# TOP_SHEET.net
KiCad netlist of a schematic drawn in Altium Designer
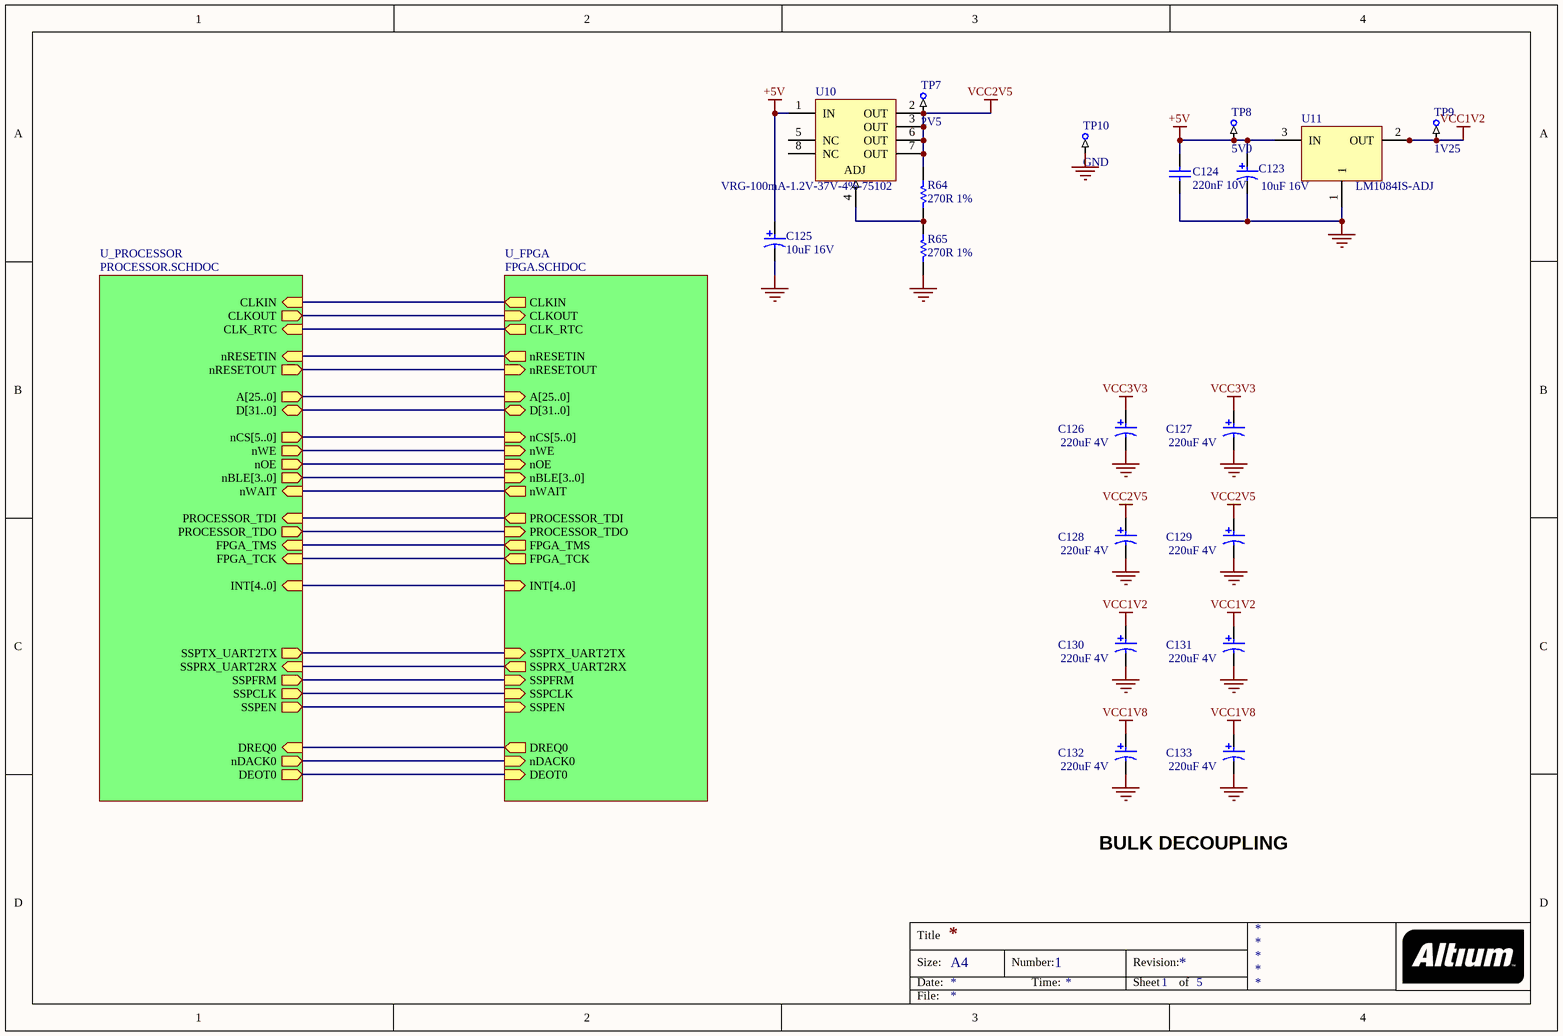
[diagram p0: TOP_SHEET.SCHDOC]

(export (version "E")
  (design (tool "Eeschema 10.0.6"))
  (components
    (comp (ref "C123")
      (value "10uF 16V")
      (footprint "CAPC3528")
      (description "Polar Capacitor")
      (libsource (lib "Altium Design Library") (part "CAP-P"))
    )
    (comp (ref "C124")
      (value "220nF 10V")
      (footprint "CAPC1608")
      (description "Capacitor")
      (libsource (lib "Altium Design Library") (part "CAP-NP"))
    )
    (comp (ref "C125")
      (value "10uF 16V")
      (footprint "CAPC3528")
      (description "Polar Capacitor")
      (libsource (lib "Altium Design Library") (part "CAP-P"))
    )
    (comp (ref "C126")
      (value "220uF 4V")
      (footprint "CAPC7343")
      (description "Polar Capacitor")
      (libsource (lib "Altium Design Library") (part "CAP-P"))
    )
    (comp (ref "C127")
      (value "220uF 4V")
      (footprint "CAPC7343")
      (description "Polar Capacitor")
      (libsource (lib "Altium Design Library") (part "CAP-P"))
    )
    (comp (ref "C128")
      (value "220uF 4V")
      (footprint "CAPC7343")
      (description "Polar Capacitor")
      (libsource (lib "Altium Design Library") (part "CAP-P"))
    )
    (comp (ref "C129")
      (value "220uF 4V")
      (footprint "CAPC7343")
      (description "Polar Capacitor")
      (libsource (lib "Altium Design Library") (part "CAP-P"))
    )
    (comp (ref "C130")
      (value "220uF 4V")
      (footprint "CAPC7343")
      (description "Polar Capacitor")
      (libsource (lib "Altium Design Library") (part "CAP-P"))
    )
    (comp (ref "C131")
      (value "220uF 4V")
      (footprint "CAPC7343")
      (description "Polar Capacitor")
      (libsource (lib "Altium Design Library") (part "CAP-P"))
    )
    (comp (ref "C132")
      (value "220uF 4V")
      (footprint "CAPC7343")
      (description "Polar Capacitor")
      (libsource (lib "Altium Design Library") (part "CAP-P"))
    )
    (comp (ref "C133")
      (value "220uF 4V")
      (footprint "CAPC7343")
      (description "Polar Capacitor")
      (libsource (lib "Altium Design Library") (part "CAP-P"))
    )
    (comp (ref "R64")
      (value "270R 1%")
      (footprint "RESC2012")
      (description "Resistor")
      (libsource (lib "Altium Design Library") (part "RES"))
    )
    (comp (ref "R65")
      (value "270R 1%")
      (footprint "RESC2012")
      (description "Resistor")
      (libsource (lib "Altium Design Library") (part "RES"))
    )
    (comp (ref "TP7")
      (value "2V5")
      (footprint "TestPin")
      (libsource (lib "Altium Design Library") (part "TestPin"))
    )
    (comp (ref "TP8")
      (value "5V0")
      (footprint "TestPin")
      (libsource (lib "Altium Design Library") (part "TestPin"))
    )
    (comp (ref "TP9")
      (value "1V25")
      (footprint "TestPin")
      (libsource (lib "Altium Design Library") (part "TestPin"))
    )
    (comp (ref "TP10")
      (value "GND")
      (footprint "TestPin")
      (libsource (lib "Altium Design Library") (part "TestPin"))
    )
    (comp (ref "U10")
      (value "VRG-100mA-1.2V-37V-4%-75102")
      (footprint "SOP127P600-8")
      (description "Low Current 3-Terminal Adjustable Positive Voltage Regulator")
      (libsource (lib "Altium Design Library") (part "VRG-ADJ-8"))
    )
    (comp (ref "U11")
      (value "LM1084IS-ADJ")
      (footprint "TO254P1435-4")
      (description "5A Low Dropout Positive Regulators")
      (libsource (lib "Altium Design Library") (part "VRG-ADJ-3"))
    )
  )
  (nets
    (net (code "1") (name "+5V") (class "Default")
      (node (ref "C123") (pin "1") (pinfunction "1_1") (pintype "passive"))
      (node (ref "C124") (pin "1") (pinfunction "1_1") (pintype "passive"))
      (node (ref "C125") (pin "1") (pinfunction "1_1") (pintype "passive"))
      (node (ref "TP8") (pin "1") (pinfunction "1_1") (pintype "input"))
      (node (ref "U10") (pin "1") (pinfunction "IN_1") (pintype "power_in"))
      (node (ref "U11") (pin "3") (pinfunction "IN_3") (pintype "power_in"))
    )
    (net (code "27") (name "GND") (class "Default")
      (node (ref "C123") (pin "2") (pinfunction "2_2") (pintype "passive"))
      (node (ref "C124") (pin "2") (pinfunction "2_2") (pintype "passive"))
      (node (ref "C125") (pin "2") (pinfunction "2_2") (pintype "passive"))
      (node (ref "C126") (pin "2") (pinfunction "2_2") (pintype "passive"))
      (node (ref "C127") (pin "2") (pinfunction "2_2") (pintype "passive"))
      (node (ref "C128") (pin "2") (pinfunction "2_2") (pintype "passive"))
      (node (ref "C129") (pin "2") (pinfunction "2_2") (pintype "passive"))
      (node (ref "C130") (pin "2") (pinfunction "2_2") (pintype "passive"))
      (node (ref "C131") (pin "2") (pinfunction "2_2") (pintype "passive"))
      (node (ref "C132") (pin "2") (pinfunction "2_2") (pintype "passive"))
      (node (ref "C133") (pin "2") (pinfunction "2_2") (pintype "passive"))
      (node (ref "R65") (pin "2") (pinfunction "2_2") (pintype "passive"))
      (node (ref "TP10") (pin "1") (pinfunction "1_1") (pintype "input"))
      (node (ref "U11") (pin "1") (pinfunction "1_1") (pintype "passive"))
    )
    (net (code "28") (name "Net-(U10-ADJ)") (class "Default")
      (node (ref "R64") (pin "2") (pinfunction "2_2") (pintype "passive"))
      (node (ref "R65") (pin "1") (pinfunction "1_1") (pintype "passive"))
      (node (ref "U10") (pin "4") (pinfunction "ADJ_4") (pintype "input"))
    )
    (net (code "29") (name "VCC1V2") (class "Default")
      (node (ref "C130") (pin "1") (pinfunction "1_1") (pintype "passive"))
      (node (ref "C131") (pin "1") (pinfunction "1_1") (pintype "passive"))
      (node (ref "TP9") (pin "1") (pinfunction "1_1") (pintype "input"))
      (node (ref "U11") (pin "2") (pinfunction "OUT_2") (pintype "power_in"))
      (node (ref "U11") (pin "4") (pinfunction "HeatSink_4") (pintype "power_in"))
    )
    (net (code "30") (name "VCC1V8") (class "Default")
      (node (ref "C132") (pin "1") (pinfunction "1_1") (pintype "passive"))
      (node (ref "C133") (pin "1") (pinfunction "1_1") (pintype "passive"))
    )
    (net (code "31") (name "VCC2V5") (class "Default")
      (node (ref "C128") (pin "1") (pinfunction "1_1") (pintype "passive"))
      (node (ref "C129") (pin "1") (pinfunction "1_1") (pintype "passive"))
      (node (ref "R64") (pin "1") (pinfunction "1_1") (pintype "passive"))
      (node (ref "TP7") (pin "1") (pinfunction "1_1") (pintype "input"))
      (node (ref "U10") (pin "2") (pinfunction "OUT_2") (pintype "power_in"))
      (node (ref "U10") (pin "3") (pinfunction "OUT_3") (pintype "power_in"))
      (node (ref "U10") (pin "6") (pinfunction "OUT_6") (pintype "power_in"))
      (node (ref "U10") (pin "7") (pinfunction "OUT_7") (pintype "power_in"))
    )
    (net (code "32") (name "VCC3V3") (class "Default")
      (node (ref "C126") (pin "1") (pinfunction "1_1") (pintype "passive"))
      (node (ref "C127") (pin "1") (pinfunction "1_1") (pintype "passive"))
    )
    (net (code "33") (name "unconnected-(U10-NC-Pad5)") (class "Default")
      (node (ref "U10") (pin "5") (pinfunction "NC_5") (pintype "passive"))
    )
    (net (code "34") (name "unconnected-(U10-NC-Pad8)") (class "Default")
      (node (ref "U10") (pin "8") (pinfunction "NC_8") (pintype "passive"))
    )
  )
)
